# MCU.net
KiCad netlist of a schematic drawn in Altium Designer
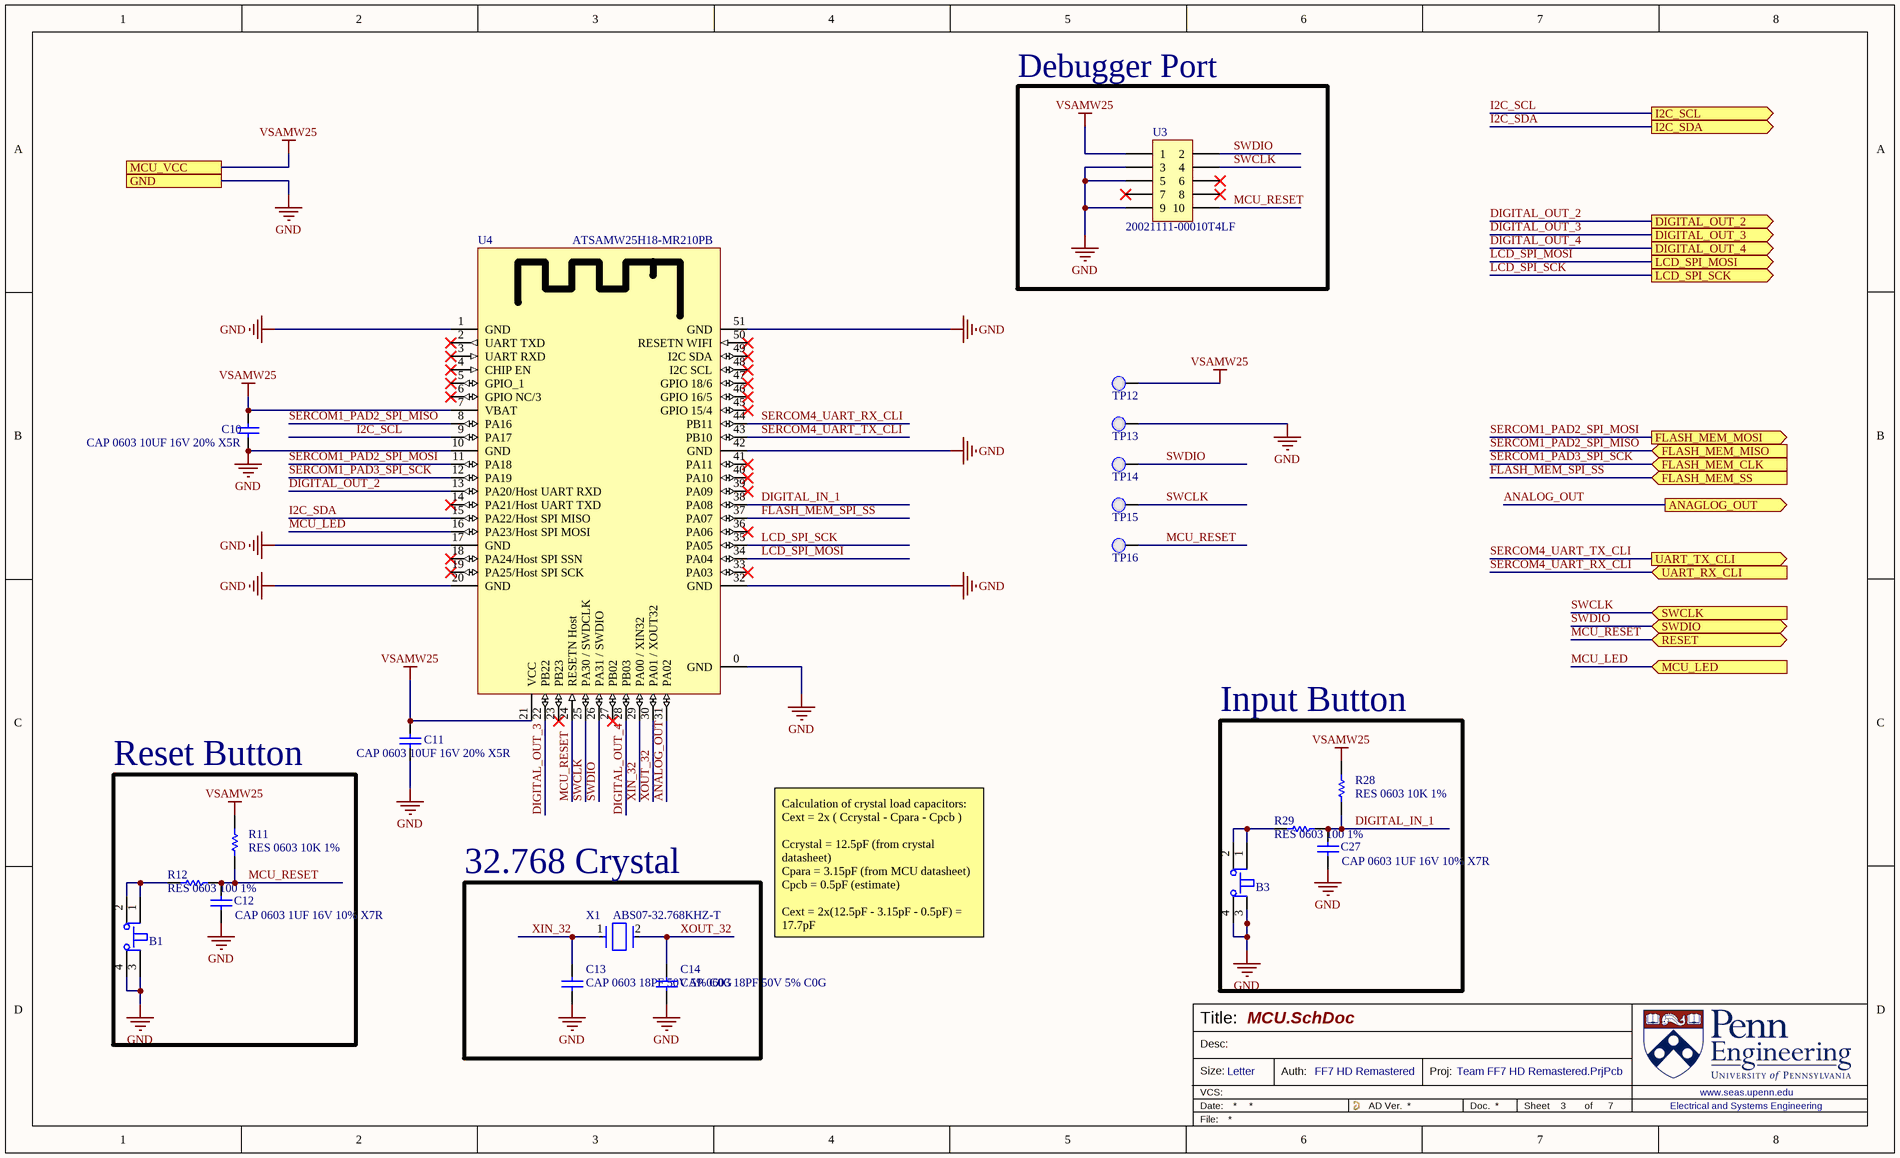
[diagram p0: MCU.SchDoc]

(export (version "E")
  (design (tool "Eeschema 10.0.6"))
  (components
    (comp (ref "B1")
      (value "PTS810SJK250SMTRLFS")
      (footprint "PTS810SJK250SMTRLFS-Footprint-1")
      (libsource (lib "University of Pennsylvania (ESE Labs)") (part "Tactile Switch 4 Pin"))
    )
    (comp (ref "B3")
      (value "PTS810SJK250SMTRLFS")
      (footprint "PTS810SJK250SMTRLFS-Footprint-1")
      (libsource (lib "University of Pennsylvania (ESE Labs)") (part "Tactile Switch 4 Pin"))
    )
    (comp (ref "C10")
      (value "CAP 0603 10UF 16V 20% X5R")
      (footprint "0603_CAP")
      (description "Capacitor Surface Mount 0603 Footprint 10UF 16V 20% Tolerance Ceramic X5R")
      (fields (field (name "MANUFACTURER") "Various"))
      (libsource (lib "University of Pennsylvania (ESE Labs)") (part "cap"))
    )
    (comp (ref "C11")
      (value "CAP 0603 10UF 16V 20% X5R")
      (footprint "0603_CAP")
      (description "Capacitor Surface Mount 0603 Footprint 10UF 16V 20% Tolerance Ceramic X5R")
      (fields (field (name "MANUFACTURER") "Various"))
      (libsource (lib "University of Pennsylvania (ESE Labs)") (part "cap"))
    )
    (comp (ref "C12")
      (value "CAP 0603 1UF 16V 10% X7R")
      (footprint "0603_CAP")
      (description "Capacitor Surface Mount 0603 Footprint 1UF 16V 10% Tolerance Ceramic X7R")
      (fields (field (name "TOLERANCE") "10%") (field (name "MANUFACTURER") "Various"))
      (libsource (lib "University of Pennsylvania (ESE Labs)") (part "cap"))
    )
    (comp (ref "C13")
      (value "CAP 0603 18PF 50V 5% C0G")
      (footprint "0603_CAP")
      (description "Capacitor Surface Mount 0603 Footprint 18PF 50V 5% Tolerance Ceramic C0G")
      (fields (field (name "VOLTAGE") "50V") (field (name "MANUFACTURER") "Various"))
      (libsource (lib "University of Pennsylvania (ESE Labs)") (part "cap"))
    )
    (comp (ref "C14")
      (value "CAP 0603 18PF 50V 5% C0G")
      (footprint "0603_CAP")
      (description "Capacitor Surface Mount 0603 Footprint 18PF 50V 5% Tolerance Ceramic C0G")
      (fields (field (name "VOLTAGE") "50V") (field (name "MANUFACTURER") "Various"))
      (libsource (lib "University of Pennsylvania (ESE Labs)") (part "cap"))
    )
    (comp (ref "C27")
      (value "CAP 0603 1UF 16V 10% X7R")
      (footprint "0603_CAP")
      (description "Capacitor Surface Mount 0603 Footprint 1UF 16V 10% Tolerance Ceramic X7R")
      (fields (field (name "TOLERANCE") "10%") (field (name "MANUFACTURER") "Various"))
      (libsource (lib "University of Pennsylvania (ESE Labs)") (part "cap"))
    )
    (comp (ref "R11")
      (value "RES 0603 10K 1%")
      (footprint "0603_RES")
      (description "Resistor Surface Mount, 10K Ohms, 0603 Footprint, 1% Tolerance 0.1W")
      (fields (field (name "TOLERANCE") "1%") (field (name "MANUFACTURER") "Various"))
      (libsource (lib "University of Pennsylvania (ESE Labs)") (part "res"))
    )
    (comp (ref "R12")
      (value "RES 0603 100 1%")
      (footprint "0603_RES")
      (description "Resistor Surface Mount, 100 Ohms, 0603 Footprint, 1% Tolerance 0.1W")
      (fields (field (name "MANUFACTURER") "Various") (field (name "TOLERANCE") "1%"))
      (libsource (lib "University of Pennsylvania (ESE Labs)") (part "res"))
    )
    (comp (ref "R28")
      (value "RES 0603 10K 1%")
      (footprint "0603_RES")
      (description "Resistor Surface Mount, 10K Ohms, 0603 Footprint, 1% Tolerance 0.1W")
      (fields (field (name "TOLERANCE") "1%") (field (name "MANUFACTURER") "Various"))
      (libsource (lib "University of Pennsylvania (ESE Labs)") (part "res"))
    )
    (comp (ref "R29")
      (value "RES 0603 100 1%")
      (footprint "0603_RES")
      (description "Resistor Surface Mount, 100 Ohms, 0603 Footprint, 1% Tolerance 0.1W")
      (fields (field (name "MANUFACTURER") "Various") (field (name "TOLERANCE") "1%"))
      (libsource (lib "University of Pennsylvania (ESE Labs)") (part "res"))
    )
    (comp (ref "TP12")
      (value "Test Point 0.1\"")
      (footprint "Test Point 0.1\"-Footprint-1")
      (libsource (lib "University of Pennsylvania (ESE Labs)") (part "Test Point 0.1{dblquote}-Symbol-1"))
    )
    (comp (ref "TP13")
      (value "Test Point 0.1\"")
      (footprint "Test Point 0.1\"-Footprint-1")
      (libsource (lib "University of Pennsylvania (ESE Labs)") (part "Test Point 0.1{dblquote}-Symbol-1"))
    )
    (comp (ref "TP14")
      (value "Test Point 0.1\"")
      (footprint "Test Point 0.1\"-Footprint-1")
      (libsource (lib "University of Pennsylvania (ESE Labs)") (part "Test Point 0.1{dblquote}-Symbol-1"))
    )
    (comp (ref "TP15")
      (value "Test Point 0.1\"")
      (footprint "Test Point 0.1\"-Footprint-1")
      (libsource (lib "University of Pennsylvania (ESE Labs)") (part "Test Point 0.1{dblquote}-Symbol-1"))
    )
    (comp (ref "TP16")
      (value "Test Point 0.1\"")
      (footprint "Test Point 0.1\"-Footprint-1")
      (libsource (lib "University of Pennsylvania (ESE Labs)") (part "Test Point 0.1{dblquote}-Symbol-1"))
    )
    (comp (ref "U3")
      (value "20021111-00010T4LF")
      (footprint "20021111-00010T4LF-Footprint-1")
      (libsource (lib "University of Pennsylvania (ESE Labs)") (part "20021111-00010T4LF-Symbol-1"))
    )
    (comp (ref "U4")
      (value "ATSAMW25H18-MR210PB")
      (footprint "SAMW25H18-MR510PB-Footprint-1")
      (description "2.7 - 4.2 V 65 Mbps 17 dbm 256 kB Flash 32 kB SRAM 802.11 b/g/n Smart Module")
      (libsource (lib "University of Pennsylvania (ESE Labs)") (part "SAMW25H18-MR510PB-Symbol-1"))
    )
    (comp (ref "X1")
      (value "ABS07-32.768KHZ-T")
      (footprint "FP-ABS07-MFG")
      (description "Crystal 32.768kHz ±20ppm (Tol) 12.5pF FUND 70kΩ 2-Pin CSMD T/R")
      (fields (field (name "TOLERANCE") "20ppm"))
      (libsource (lib "Altium Content Vault") (part "c23a69dc6c9e2f18f2079038eb95dd1"))
    )
  )
  (nets
    (net (code "1") (name "/ANALOG_OUT") (class "Default")
      (node (ref "U4") (pin "31") (pinfunction "PA02_31") (pintype "bidirectional"))
    )
    (net (code "2") (name "/DIGITAL_IN_1") (class "Default")
      (node (ref "C27") (pin "2") (pinfunction "2_2") (pintype "passive"))
      (node (ref "R28") (pin "1") (pinfunction "1_1") (pintype "passive"))
      (node (ref "R29") (pin "2") (pinfunction "2_2") (pintype "passive"))
      (node (ref "U4") (pin "38") (pinfunction "PA08_38") (pintype "bidirectional"))
    )
    (net (code "3") (name "/DIGITAL_OUT_2") (class "Default")
      (node (ref "U4") (pin "13") (pinfunction "PA20/Host_UART_RXD_13") (pintype "bidirectional"))
    )
    (net (code "4") (name "/DIGITAL_OUT_3") (class "Default")
      (node (ref "U4") (pin "22") (pinfunction "PB22_22") (pintype "bidirectional"))
    )
    (net (code "5") (name "/DIGITAL_OUT_4") (class "Default")
      (node (ref "U4") (pin "28") (pinfunction "PB03_28") (pintype "bidirectional"))
    )
    (net (code "6") (name "/FLASH_MEM_SPI_SS") (class "Default")
      (node (ref "U4") (pin "37") (pinfunction "PA07_37") (pintype "bidirectional"))
    )
    (net (code "7") (name "/I2C_SCL") (class "Default")
      (node (ref "U4") (pin "9") (pinfunction "PA17_9") (pintype "bidirectional"))
    )
    (net (code "8") (name "/I2C_SDA") (class "Default")
      (node (ref "U4") (pin "15") (pinfunction "PA22/Host_SPI_MISO_15") (pintype "bidirectional"))
    )
    (net (code "9") (name "/LCD_SPI_MOSI") (class "Default")
      (node (ref "U4") (pin "34") (pinfunction "PA04_34") (pintype "bidirectional"))
    )
    (net (code "10") (name "/LCD_SPI_SCK") (class "Default")
      (node (ref "U4") (pin "35") (pinfunction "PA05_35") (pintype "bidirectional"))
    )
    (net (code "11") (name "/MCU_LED") (class "Default")
      (node (ref "U4") (pin "16") (pinfunction "PA23/Host_SPI_MOSI_16") (pintype "bidirectional"))
    )
    (net (code "12") (name "/MCU_RESET") (class "Default")
      (node (ref "C12") (pin "2") (pinfunction "2_2") (pintype "passive"))
      (node (ref "R11") (pin "1") (pinfunction "1_1") (pintype "passive"))
      (node (ref "R12") (pin "2") (pinfunction "2_2") (pintype "passive"))
      (node (ref "TP16") (pin "1") (pinfunction "PAD_1") (pintype "passive"))
      (node (ref "U3") (pin "10") (pinfunction "10_10") (pintype "passive"))
      (node (ref "U4") (pin "24") (pinfunction "RESETN_Host_24") (pintype "input"))
    )
    (net (code "13") (name "/SERCOM1_PAD2_SPI_MISO") (class "Default")
      (node (ref "U4") (pin "8") (pinfunction "PA16_8") (pintype "bidirectional"))
    )
    (net (code "14") (name "/SERCOM1_PAD2_SPI_MOSI") (class "Default")
      (node (ref "U4") (pin "11") (pinfunction "PA18_11") (pintype "bidirectional"))
    )
    (net (code "15") (name "/SERCOM1_PAD3_SPI_SCK") (class "Default")
      (node (ref "U4") (pin "12") (pinfunction "PA19_12") (pintype "bidirectional"))
    )
    (net (code "16") (name "/SERCOM4_UART_RX_CLI") (class "Default")
      (node (ref "U4") (pin "44") (pinfunction "PB11_44") (pintype "bidirectional"))
    )
    (net (code "17") (name "/SERCOM4_UART_TX_CLI") (class "Default")
      (node (ref "U4") (pin "43") (pinfunction "PB10_43") (pintype "bidirectional"))
    )
    (net (code "18") (name "/SWCLK") (class "Default")
      (node (ref "TP15") (pin "1") (pinfunction "PAD_1") (pintype "passive"))
      (node (ref "U3") (pin "4") (pinfunction "4_4") (pintype "passive"))
      (node (ref "U4") (pin "25") (pinfunction "PA30_/_SWDCLK_25") (pintype "bidirectional"))
    )
    (net (code "19") (name "/SWDIO") (class "Default")
      (node (ref "TP14") (pin "1") (pinfunction "PAD_1") (pintype "passive"))
      (node (ref "U3") (pin "2") (pinfunction "2_2") (pintype "passive"))
      (node (ref "U4") (pin "26") (pinfunction "PA31_/_SWDIO_26") (pintype "bidirectional"))
    )
    (net (code "20") (name "/XIN_32") (class "Default")
      (node (ref "C13") (pin "2") (pinfunction "2_2") (pintype "passive"))
      (node (ref "U4") (pin "29") (pinfunction "PA00_/_XIN32_29") (pintype "bidirectional"))
      (node (ref "X1") (pin "1") (pinfunction "1_1") (pintype "passive"))
    )
    (net (code "21") (name "/XOUT_32") (class "Default")
      (node (ref "C14") (pin "2") (pinfunction "2_2") (pintype "passive"))
      (node (ref "U4") (pin "30") (pinfunction "PA01_/_XOUT32_30") (pintype "bidirectional"))
      (node (ref "X1") (pin "2") (pinfunction "2_2") (pintype "passive"))
    )
    (net (code "22") (name "GND") (class "Default")
      (node (ref "B1") (pin "3") (pinfunction "2_3") (pintype "passive"))
      (node (ref "B1") (pin "4") (pinfunction "4_4") (pintype "passive"))
      (node (ref "B3") (pin "3") (pinfunction "2_3") (pintype "passive"))
      (node (ref "B3") (pin "4") (pinfunction "4_4") (pintype "passive"))
      (node (ref "C10") (pin "1") (pinfunction "1_1") (pintype "passive"))
      (node (ref "C11") (pin "1") (pinfunction "1_1") (pintype "passive"))
      (node (ref "C12") (pin "1") (pinfunction "1_1") (pintype "passive"))
      (node (ref "C13") (pin "1") (pinfunction "1_1") (pintype "passive"))
      (node (ref "C14") (pin "1") (pinfunction "1_1") (pintype "passive"))
      (node (ref "C27") (pin "1") (pinfunction "1_1") (pintype "passive"))
      (node (ref "TP13") (pin "1") (pinfunction "PAD_1") (pintype "passive"))
      (node (ref "U3") (pin "3") (pinfunction "3_3") (pintype "passive"))
      (node (ref "U3") (pin "5") (pinfunction "5_5") (pintype "passive"))
      (node (ref "U3") (pin "9") (pinfunction "9_9") (pintype "passive"))
      (node (ref "U4") (pin "0") (pinfunction "GND_0") (pintype "power_in"))
      (node (ref "U4") (pin "1") (pinfunction "GND_1") (pintype "power_in"))
      (node (ref "U4") (pin "10") (pinfunction "GND_10") (pintype "power_in"))
      (node (ref "U4") (pin "17") (pinfunction "GND_17") (pintype "power_in"))
      (node (ref "U4") (pin "20") (pinfunction "GND_20") (pintype "power_in"))
      (node (ref "U4") (pin "32") (pinfunction "GND_32") (pintype "power_in"))
      (node (ref "U4") (pin "42") (pinfunction "GND_42") (pintype "power_in"))
      (node (ref "U4") (pin "51") (pinfunction "GND_51") (pintype "power_in"))
    )
    (net (code "23") (name "Net-(B1-Pad1)") (class "Default")
      (node (ref "B1") (pin "1") (pinfunction "1_1") (pintype "passive"))
      (node (ref "B1") (pin "2") (pinfunction "2_2") (pintype "passive"))
      (node (ref "R12") (pin "1") (pinfunction "1_1") (pintype "passive"))
    )
    (net (code "24") (name "Net-(B3-Pad1)") (class "Default")
      (node (ref "B3") (pin "1") (pinfunction "1_1") (pintype "passive"))
      (node (ref "B3") (pin "2") (pinfunction "2_2") (pintype "passive"))
      (node (ref "R29") (pin "1") (pinfunction "1_1") (pintype "passive"))
    )
    (net (code "25") (name "VSAMW25") (class "Default")
      (node (ref "C10") (pin "2") (pinfunction "2_2") (pintype "passive"))
      (node (ref "C11") (pin "2") (pinfunction "2_2") (pintype "passive"))
      (node (ref "R11") (pin "2") (pinfunction "2_2") (pintype "passive"))
      (node (ref "R28") (pin "2") (pinfunction "2_2") (pintype "passive"))
      (node (ref "TP12") (pin "1") (pinfunction "PAD_1") (pintype "passive"))
      (node (ref "U3") (pin "1") (pinfunction "1_1") (pintype "passive"))
      (node (ref "U4") (pin "21") (pinfunction "VCC_21") (pintype "power_in"))
      (node (ref "U4") (pin "7") (pinfunction "VBAT_7") (pintype "power_in"))
    )
    (net (code "26") (name "unconnected-(U3-Pad6)") (class "Default")
      (node (ref "U3") (pin "6") (pinfunction "6_6") (pintype "passive+no_connect"))
    )
    (net (code "27") (name "unconnected-(U3-Pad7)") (class "Default")
      (node (ref "U3") (pin "7") (pinfunction "7_7") (pintype "passive+no_connect"))
    )
    (net (code "28") (name "unconnected-(U3-Pad8)") (class "Default")
      (node (ref "U3") (pin "8") (pinfunction "8_8") (pintype "passive+no_connect"))
    )
    (net (code "29") (name "unconnected-(U4-CHIP_EN-Pad4)") (class "Default")
      (node (ref "U4") (pin "4") (pinfunction "CHIP_EN_4") (pintype "input+no_connect"))
    )
    (net (code "30") (name "unconnected-(U4-GPIO_1-Pad5)") (class "Default")
      (node (ref "U4") (pin "5") (pinfunction "GPIO_1_5") (pintype "bidirectional+no_connect"))
    )
    (net (code "31") (name "unconnected-(U4-GPIO_15{slash}4-Pad45)") (class "Default")
      (node (ref "U4") (pin "45") (pinfunction "GPIO_15/4_45") (pintype "bidirectional+no_connect"))
    )
    (net (code "32") (name "unconnected-(U4-GPIO_16{slash}5-Pad46)") (class "Default")
      (node (ref "U4") (pin "46") (pinfunction "GPIO_16/5_46") (pintype "bidirectional+no_connect"))
    )
    (net (code "33") (name "unconnected-(U4-GPIO_18{slash}6-Pad47)") (class "Default")
      (node (ref "U4") (pin "47") (pinfunction "GPIO_18/6_47") (pintype "bidirectional+no_connect"))
    )
    (net (code "34") (name "unconnected-(U4-GPIO_NC{slash}3-Pad6)") (class "Default")
      (node (ref "U4") (pin "6") (pinfunction "GPIO_NC/3_6") (pintype "bidirectional+no_connect"))
    )
    (net (code "35") (name "unconnected-(U4-I2C_SCL-Pad48)") (class "Default")
      (node (ref "U4") (pin "48") (pinfunction "I2C_SCL_48") (pintype "bidirectional+no_connect"))
    )
    (net (code "36") (name "unconnected-(U4-I2C_SDA-Pad49)") (class "Default")
      (node (ref "U4") (pin "49") (pinfunction "I2C_SDA_49") (pintype "bidirectional+no_connect"))
    )
    (net (code "37") (name "unconnected-(U4-PA03-Pad33)") (class "Default")
      (node (ref "U4") (pin "33") (pinfunction "PA03_33") (pintype "bidirectional+no_connect"))
    )
    (net (code "38") (name "unconnected-(U4-PA06-Pad36)") (class "Default")
      (node (ref "U4") (pin "36") (pinfunction "PA06_36") (pintype "bidirectional+no_connect"))
    )
    (net (code "39") (name "unconnected-(U4-PA09-Pad39)") (class "Default")
      (node (ref "U4") (pin "39") (pinfunction "PA09_39") (pintype "bidirectional+no_connect"))
    )
    (net (code "40") (name "unconnected-(U4-PA10-Pad40)") (class "Default")
      (node (ref "U4") (pin "40") (pinfunction "PA10_40") (pintype "bidirectional+no_connect"))
    )
    (net (code "41") (name "unconnected-(U4-PA11-Pad41)") (class "Default")
      (node (ref "U4") (pin "41") (pinfunction "PA11_41") (pintype "bidirectional+no_connect"))
    )
    (net (code "42") (name "unconnected-(U4-PA21{slash}Host_UART_TXD-Pad14)") (class "Default")
      (node (ref "U4") (pin "14") (pinfunction "PA21/Host_UART_TXD_14") (pintype "bidirectional+no_connect"))
    )
    (net (code "43") (name "unconnected-(U4-PA24{slash}Host_SPI_SSN-Pad18)") (class "Default")
      (node (ref "U4") (pin "18") (pinfunction "PA24/Host_SPI_SSN_18") (pintype "bidirectional+no_connect"))
    )
    (net (code "44") (name "unconnected-(U4-PA25{slash}Host_SPI_SCK-Pad19)") (class "Default")
      (node (ref "U4") (pin "19") (pinfunction "PA25/Host_SPI_SCK_19") (pintype "bidirectional+no_connect"))
    )
    (net (code "45") (name "unconnected-(U4-PB02-Pad27)") (class "Default")
      (node (ref "U4") (pin "27") (pinfunction "PB02_27") (pintype "bidirectional+no_connect"))
    )
    (net (code "46") (name "unconnected-(U4-PB23-Pad23)") (class "Default")
      (node (ref "U4") (pin "23") (pinfunction "PB23_23") (pintype "bidirectional+no_connect"))
    )
    (net (code "47") (name "unconnected-(U4-RESETN_WIFI-Pad50)") (class "Default")
      (node (ref "U4") (pin "50") (pinfunction "RESETN_WIFI_50") (pintype "input+no_connect"))
    )
    (net (code "48") (name "unconnected-(U4-UART_RXD-Pad3)") (class "Default")
      (node (ref "U4") (pin "3") (pinfunction "UART_RXD_3") (pintype "input+no_connect"))
    )
    (net (code "49") (name "unconnected-(U4-UART_TXD-Pad2)") (class "Default")
      (node (ref "U4") (pin "2") (pinfunction "UART_TXD_2") (pintype "output+no_connect"))
    )
  )
)
